# Rectifi-Presicion-Doble.net
KiCad netlist of a schematic drawn in EAGLE
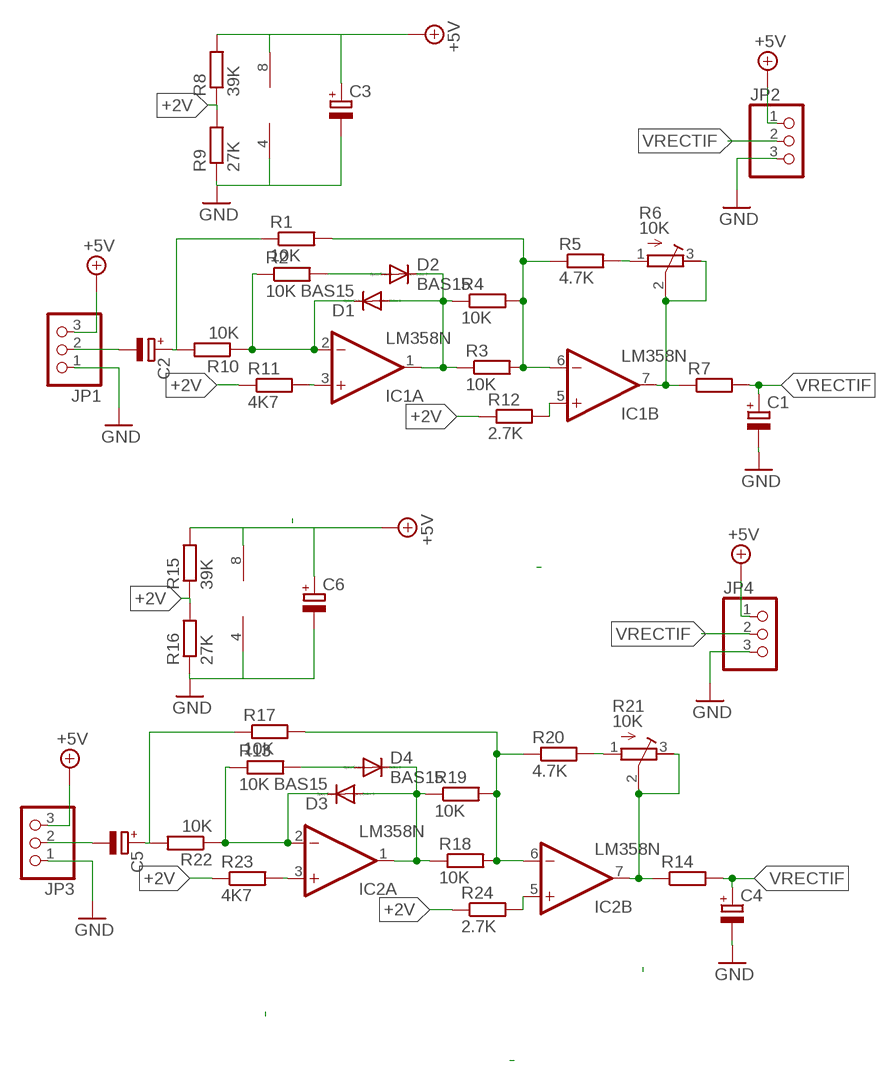
[diagram p0: schematic, sheet 1]

(export (version "E")
  (design (tool "Eeschema 10.0.6"))
  (components
    (comp (ref "C1")
      (value "CPOL-EUE2.5-5")
      (footprint "eagle-import:E2,5-5")
      (libsource (lib "eagle-import") (part "CPOL-EUE2.5-5"))
    )
    (comp (ref "C2")
      (value "CPOL-EUE2.5-5")
      (footprint "eagle-import:E2,5-5")
      (libsource (lib "eagle-import") (part "CPOL-EUE2.5-5"))
    )
    (comp (ref "C3")
      (value "CPOL-EUE2.5-6")
      (footprint "eagle-import:E2,5-6")
      (libsource (lib "eagle-import") (part "CPOL-EUE2.5-6"))
    )
    (comp (ref "C4")
      (value "CPOL-EUE2.5-5")
      (footprint "eagle-import:E2,5-5")
      (libsource (lib "eagle-import") (part "CPOL-EUE2.5-5"))
    )
    (comp (ref "C5")
      (value "CPOL-EUE2.5-5")
      (footprint "eagle-import:E2,5-5")
      (libsource (lib "eagle-import") (part "CPOL-EUE2.5-5"))
    )
    (comp (ref "C6")
      (value "CPOL-EUE2.5-6")
      (footprint "eagle-import:E2,5-6")
      (libsource (lib "eagle-import") (part "CPOL-EUE2.5-6"))
    )
    (comp (ref "D1")
      (value "BAS15")
      (footprint "eagle-import:DO34-7")
      (libsource (lib "eagle-import") (part "BAS15"))
    )
    (comp (ref "D2")
      (value "BAS15")
      (footprint "eagle-import:DO34-7")
      (libsource (lib "eagle-import") (part "BAS15"))
    )
    (comp (ref "D3")
      (value "BAS15")
      (footprint "eagle-import:DO34-7")
      (libsource (lib "eagle-import") (part "BAS15"))
    )
    (comp (ref "D4")
      (value "BAS15")
      (footprint "eagle-import:DO34-7")
      (libsource (lib "eagle-import") (part "BAS15"))
    )
    (comp (ref "IC1")
      (value "LM358N")
      (footprint "eagle-import:DIL08")
      (libsource (lib "eagle-import") (part "LM358N"))
    )
    (comp (ref "IC2")
      (value "LM358N")
      (footprint "eagle-import:DIL08")
      (libsource (lib "eagle-import") (part "LM358N"))
    )
    (comp (ref "JP1")
      (value "PINHD-1X3")
      (footprint "eagle-import:1X03")
      (libsource (lib "eagle-import") (part "PINHD-1X3"))
    )
    (comp (ref "JP2")
      (value "PINHD-1X3")
      (footprint "eagle-import:1X03")
      (libsource (lib "eagle-import") (part "PINHD-1X3"))
    )
    (comp (ref "JP3")
      (value "PINHD-1X3")
      (footprint "eagle-import:1X03")
      (libsource (lib "eagle-import") (part "PINHD-1X3"))
    )
    (comp (ref "JP4")
      (value "PINHD-1X3")
      (footprint "eagle-import:1X03")
      (libsource (lib "eagle-import") (part "PINHD-1X3"))
    )
    (comp (ref "R1")
      (value "10K")
      (footprint "eagle-import:0207_7")
      (libsource (lib "eagle-import") (part "R-EU_0207/7"))
    )
    (comp (ref "R2")
      (value "10K")
      (footprint "eagle-import:0207_7")
      (libsource (lib "eagle-import") (part "R-EU_0207/7"))
    )
    (comp (ref "R3")
      (value "10K")
      (footprint "eagle-import:0207_7")
      (libsource (lib "eagle-import") (part "R-EU_0207/7"))
    )
    (comp (ref "R4")
      (value "10K")
      (footprint "eagle-import:0207_7")
      (libsource (lib "eagle-import") (part "R-EU_0207/7"))
    )
    (comp (ref "R5")
      (value "4.7K")
      (footprint "eagle-import:0207_7")
      (libsource (lib "eagle-import") (part "R-EU_0207/7"))
    )
    (comp (ref "R6")
      (value "10K")
      (footprint "eagle-import:RTRIM64W")
      (libsource (lib "eagle-import") (part "R-TRIMM64W"))
    )
    (comp (ref "R7")
      (value "R-EU_0207/7")
      (footprint "eagle-import:0207_7")
      (libsource (lib "eagle-import") (part "R-EU_0207/7"))
    )
    (comp (ref "R8")
      (value "39K")
      (footprint "eagle-import:0207_7")
      (libsource (lib "eagle-import") (part "R-EU_0207/7"))
    )
    (comp (ref "R9")
      (value "27K")
      (footprint "eagle-import:0207_7")
      (libsource (lib "eagle-import") (part "R-EU_0207/7"))
    )
    (comp (ref "R10")
      (value "10K")
      (footprint "eagle-import:0207_7")
      (libsource (lib "eagle-import") (part "R-EU_0207/7"))
    )
    (comp (ref "R11")
      (value "4K7")
      (footprint "eagle-import:0207_7")
      (libsource (lib "eagle-import") (part "R-EU_0207/7"))
    )
    (comp (ref "R12")
      (value "2.7K")
      (footprint "eagle-import:0207_7")
      (libsource (lib "eagle-import") (part "R-EU_0207/7"))
    )
    (comp (ref "R13")
      (value "10K")
      (footprint "eagle-import:0207_7")
      (libsource (lib "eagle-import") (part "R-EU_0207/7"))
    )
    (comp (ref "R14")
      (value "R-EU_0207/7")
      (footprint "eagle-import:0207_7")
      (libsource (lib "eagle-import") (part "R-EU_0207/7"))
    )
    (comp (ref "R15")
      (value "39K")
      (footprint "eagle-import:0207_7")
      (libsource (lib "eagle-import") (part "R-EU_0207/7"))
    )
    (comp (ref "R16")
      (value "27K")
      (footprint "eagle-import:0207_7")
      (libsource (lib "eagle-import") (part "R-EU_0207/7"))
    )
    (comp (ref "R17")
      (value "10K")
      (footprint "eagle-import:0207_7")
      (libsource (lib "eagle-import") (part "R-EU_0207/7"))
    )
    (comp (ref "R18")
      (value "10K")
      (footprint "eagle-import:0207_7")
      (libsource (lib "eagle-import") (part "R-EU_0207/7"))
    )
    (comp (ref "R19")
      (value "10K")
      (footprint "eagle-import:0207_7")
      (libsource (lib "eagle-import") (part "R-EU_0207/7"))
    )
    (comp (ref "R20")
      (value "4.7K")
      (footprint "eagle-import:0207_7")
      (libsource (lib "eagle-import") (part "R-EU_0207/7"))
    )
    (comp (ref "R21")
      (value "10K")
      (footprint "eagle-import:RTRIM64W")
      (libsource (lib "eagle-import") (part "R-TRIMM64W"))
    )
    (comp (ref "R22")
      (value "10K")
      (footprint "eagle-import:0207_7")
      (libsource (lib "eagle-import") (part "R-EU_0207/7"))
    )
    (comp (ref "R23")
      (value "4K7")
      (footprint "eagle-import:0207_7")
      (libsource (lib "eagle-import") (part "R-EU_0207/7"))
    )
    (comp (ref "R24")
      (value "2.7K")
      (footprint "eagle-import:0207_7")
      (libsource (lib "eagle-import") (part "R-EU_0207/7"))
    )
  )
  (nets
    (net (code "1") (name "+2V") (class "Default")
      (node (ref "R11") (pin "1") (pinfunction "1_1") (pintype "passive"))
      (node (ref "R12") (pin "1") (pinfunction "1_1") (pintype "passive"))
      (node (ref "R15") (pin "1") (pinfunction "1_1") (pintype "passive"))
      (node (ref "R16") (pin "2") (pinfunction "2_2") (pintype "passive"))
      (node (ref "R23") (pin "1") (pinfunction "1_1") (pintype "passive"))
      (node (ref "R24") (pin "1") (pinfunction "1_1") (pintype "passive"))
      (node (ref "R8") (pin "1") (pinfunction "1_1") (pintype "passive"))
      (node (ref "R9") (pin "2") (pinfunction "2_2") (pintype "passive"))
    )
    (net (code "2") (name "+5V") (class "Default")
      (node (ref "C3") (pin "+") (pinfunction "+_+") (pintype "passive"))
      (node (ref "C6") (pin "+") (pinfunction "+_+") (pintype "passive"))
      (node (ref "IC1") (pin "8") (pinfunction "V+_8") (pintype "power_in"))
      (node (ref "IC2") (pin "8") (pinfunction "V+_8") (pintype "power_in"))
      (node (ref "JP1") (pin "3") (pinfunction "3_3") (pintype "passive"))
      (node (ref "JP2") (pin "1") (pinfunction "1_1") (pintype "passive"))
      (node (ref "JP3") (pin "3") (pinfunction "3_3") (pintype "passive"))
      (node (ref "JP4") (pin "1") (pinfunction "1_1") (pintype "passive"))
      (node (ref "R15") (pin "2") (pinfunction "2_2") (pintype "passive"))
      (node (ref "R8") (pin "2") (pinfunction "2_2") (pintype "passive"))
    )
    (net (code "3") (name "GND") (class "Default")
      (node (ref "C1") (pin "-") (pinfunction "-_-") (pintype "passive"))
      (node (ref "C3") (pin "-") (pinfunction "-_-") (pintype "passive"))
      (node (ref "C4") (pin "-") (pinfunction "-_-") (pintype "passive"))
      (node (ref "C6") (pin "-") (pinfunction "-_-") (pintype "passive"))
      (node (ref "IC1") (pin "4") (pinfunction "V-_4") (pintype "power_in"))
      (node (ref "IC2") (pin "4") (pinfunction "V-_4") (pintype "power_in"))
      (node (ref "JP1") (pin "1") (pinfunction "1_1") (pintype "passive"))
      (node (ref "JP2") (pin "3") (pinfunction "3_3") (pintype "passive"))
      (node (ref "JP3") (pin "1") (pinfunction "1_1") (pintype "passive"))
      (node (ref "JP4") (pin "3") (pinfunction "3_3") (pintype "passive"))
      (node (ref "R16") (pin "1") (pinfunction "1_1") (pintype "passive"))
      (node (ref "R9") (pin "1") (pinfunction "1_1") (pintype "passive"))
    )
    (net (code "4") (name "Net-(C2-Pad+)") (class "Default")
      (node (ref "C2") (pin "+") (pinfunction "+_+") (pintype "passive"))
      (node (ref "R1") (pin "1") (pinfunction "1_1") (pintype "passive"))
      (node (ref "R10") (pin "2") (pinfunction "2_2") (pintype "passive"))
    )
    (net (code "5") (name "Net-(C2-Pad-)") (class "Default")
      (node (ref "C2") (pin "-") (pinfunction "-_-") (pintype "passive"))
      (node (ref "JP1") (pin "2") (pinfunction "2_2") (pintype "passive"))
    )
    (net (code "6") (name "Net-(C5-Pad+)") (class "Default")
      (node (ref "C5") (pin "+") (pinfunction "+_+") (pintype "passive"))
      (node (ref "R17") (pin "1") (pinfunction "1_1") (pintype "passive"))
      (node (ref "R22") (pin "2") (pinfunction "2_2") (pintype "passive"))
    )
    (net (code "7") (name "Net-(C5-Pad-)") (class "Default")
      (node (ref "C5") (pin "-") (pinfunction "-_-") (pintype "passive"))
      (node (ref "JP3") (pin "2") (pinfunction "2_2") (pintype "passive"))
    )
    (net (code "8") (name "Net-(D2-PadA)") (class "Default")
      (node (ref "D2") (pin "A") (pinfunction "A_A") (pintype "passive"))
      (node (ref "R2") (pin "2") (pinfunction "2_2") (pintype "passive"))
    )
    (net (code "9") (name "Net-(D4-PadA)") (class "Default")
      (node (ref "D4") (pin "A") (pinfunction "A_A") (pintype "passive"))
      (node (ref "R13") (pin "2") (pinfunction "2_2") (pintype "passive"))
    )
    (net (code "10") (name "Net-(IC1A-+IN)") (class "Default")
      (node (ref "IC1") (pin "3") (pinfunction "+IN_3") (pintype "input"))
      (node (ref "R11") (pin "2") (pinfunction "2_2") (pintype "passive"))
    )
    (net (code "11") (name "Net-(IC1A--IN)") (class "Default")
      (node (ref "D1") (pin "C") (pinfunction "C_C") (pintype "passive"))
      (node (ref "IC1") (pin "2") (pinfunction "-IN_2") (pintype "input"))
      (node (ref "R10") (pin "1") (pinfunction "1_1") (pintype "passive"))
      (node (ref "R2") (pin "1") (pinfunction "1_1") (pintype "passive"))
    )
    (net (code "12") (name "Net-(IC1A-OUT)") (class "Default")
      (node (ref "D1") (pin "A") (pinfunction "A_A") (pintype "passive"))
      (node (ref "D2") (pin "C") (pinfunction "C_C") (pintype "passive"))
      (node (ref "IC1") (pin "1") (pinfunction "OUT_1") (pintype "output"))
      (node (ref "R3") (pin "1") (pinfunction "1_1") (pintype "passive"))
      (node (ref "R4") (pin "1") (pinfunction "1_1") (pintype "passive"))
    )
    (net (code "13") (name "Net-(IC1B-+IN)") (class "Default")
      (node (ref "IC1") (pin "5") (pinfunction "+IN_5") (pintype "input"))
      (node (ref "R12") (pin "2") (pinfunction "2_2") (pintype "passive"))
    )
    (net (code "14") (name "Net-(IC1B--IN)") (class "Default")
      (node (ref "IC1") (pin "6") (pinfunction "-IN_6") (pintype "input"))
      (node (ref "R1") (pin "2") (pinfunction "2_2") (pintype "passive"))
      (node (ref "R3") (pin "2") (pinfunction "2_2") (pintype "passive"))
      (node (ref "R4") (pin "2") (pinfunction "2_2") (pintype "passive"))
      (node (ref "R5") (pin "1") (pinfunction "1_1") (pintype "passive"))
    )
    (net (code "15") (name "Net-(IC1B-OUT)") (class "Default")
      (node (ref "IC1") (pin "7") (pinfunction "OUT_7") (pintype "output"))
      (node (ref "R6") (pin "2") (pinfunction "S_2") (pintype "passive"))
      (node (ref "R6") (pin "3") (pinfunction "E_3") (pintype "passive"))
      (node (ref "R7") (pin "1") (pinfunction "1_1") (pintype "passive"))
    )
    (net (code "16") (name "Net-(IC2A-+IN)") (class "Default")
      (node (ref "IC2") (pin "3") (pinfunction "+IN_3") (pintype "input"))
      (node (ref "R23") (pin "2") (pinfunction "2_2") (pintype "passive"))
    )
    (net (code "17") (name "Net-(IC2A--IN)") (class "Default")
      (node (ref "D3") (pin "C") (pinfunction "C_C") (pintype "passive"))
      (node (ref "IC2") (pin "2") (pinfunction "-IN_2") (pintype "input"))
      (node (ref "R13") (pin "1") (pinfunction "1_1") (pintype "passive"))
      (node (ref "R22") (pin "1") (pinfunction "1_1") (pintype "passive"))
    )
    (net (code "18") (name "Net-(IC2A-OUT)") (class "Default")
      (node (ref "D3") (pin "A") (pinfunction "A_A") (pintype "passive"))
      (node (ref "D4") (pin "C") (pinfunction "C_C") (pintype "passive"))
      (node (ref "IC2") (pin "1") (pinfunction "OUT_1") (pintype "output"))
      (node (ref "R18") (pin "1") (pinfunction "1_1") (pintype "passive"))
      (node (ref "R19") (pin "1") (pinfunction "1_1") (pintype "passive"))
    )
    (net (code "19") (name "Net-(IC2B-+IN)") (class "Default")
      (node (ref "IC2") (pin "5") (pinfunction "+IN_5") (pintype "input"))
      (node (ref "R24") (pin "2") (pinfunction "2_2") (pintype "passive"))
    )
    (net (code "20") (name "Net-(IC2B--IN)") (class "Default")
      (node (ref "IC2") (pin "6") (pinfunction "-IN_6") (pintype "input"))
      (node (ref "R17") (pin "2") (pinfunction "2_2") (pintype "passive"))
      (node (ref "R18") (pin "2") (pinfunction "2_2") (pintype "passive"))
      (node (ref "R19") (pin "2") (pinfunction "2_2") (pintype "passive"))
      (node (ref "R20") (pin "1") (pinfunction "1_1") (pintype "passive"))
    )
    (net (code "21") (name "Net-(IC2B-OUT)") (class "Default")
      (node (ref "IC2") (pin "7") (pinfunction "OUT_7") (pintype "output"))
      (node (ref "R14") (pin "1") (pinfunction "1_1") (pintype "passive"))
      (node (ref "R21") (pin "2") (pinfunction "S_2") (pintype "passive"))
      (node (ref "R21") (pin "3") (pinfunction "E_3") (pintype "passive"))
    )
    (net (code "22") (name "Net-(R6-A)") (class "Default")
      (node (ref "R5") (pin "2") (pinfunction "2_2") (pintype "passive"))
      (node (ref "R6") (pin "1") (pinfunction "A_1") (pintype "passive"))
    )
    (net (code "23") (name "Net-(R21-A)") (class "Default")
      (node (ref "R20") (pin "2") (pinfunction "2_2") (pintype "passive"))
      (node (ref "R21") (pin "1") (pinfunction "A_1") (pintype "passive"))
    )
    (net (code "24") (name "VRECTIF") (class "Default")
      (node (ref "C1") (pin "+") (pinfunction "+_+") (pintype "passive"))
      (node (ref "C4") (pin "+") (pinfunction "+_+") (pintype "passive"))
      (node (ref "JP2") (pin "2") (pinfunction "2_2") (pintype "passive"))
      (node (ref "JP4") (pin "2") (pinfunction "2_2") (pintype "passive"))
      (node (ref "R14") (pin "2") (pinfunction "2_2") (pintype "passive"))
      (node (ref "R7") (pin "2") (pinfunction "2_2") (pintype "passive"))
    )
  )
)
